# MCU152A_ADC.net
KiCad netlist of a schematic drawn in Altium Designer
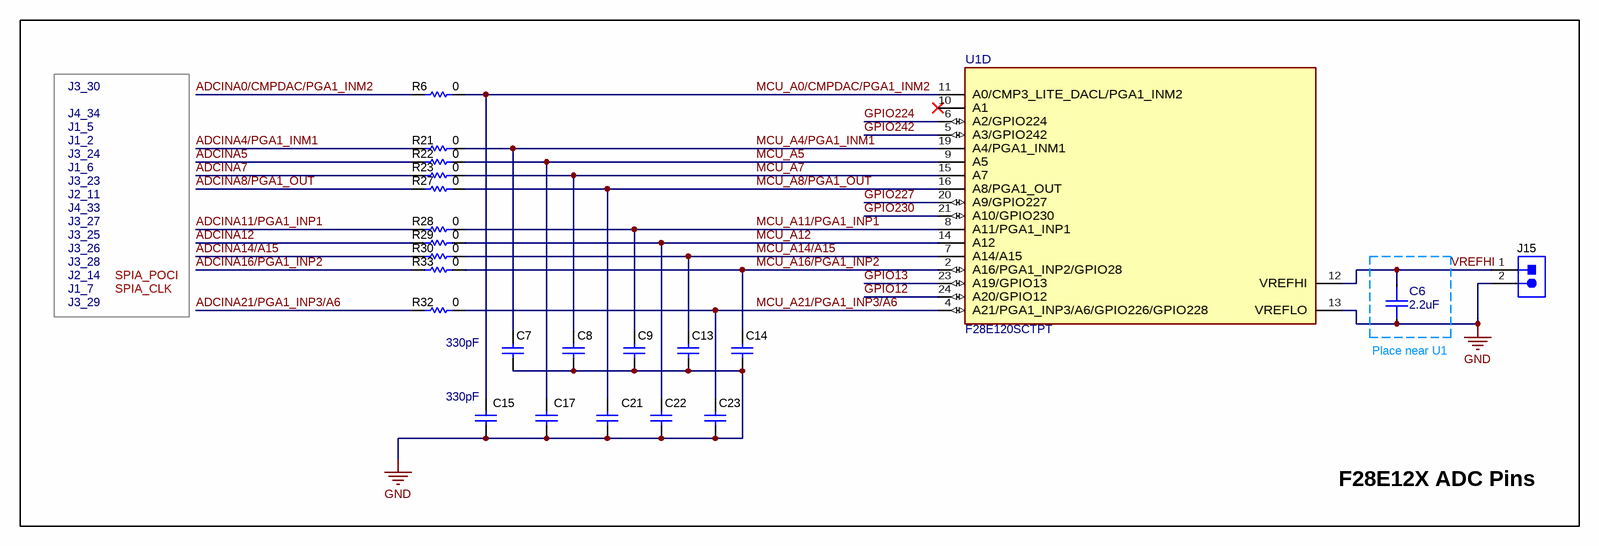
[diagram p0: MCU152A_ADC.SchDoc]

(export (version "E")
  (design (tool "Eeschema 10.0.6"))
  (components
    (comp (ref "C6")
      (value "885012106011")
      (footprint "FP-885012106011_0603-MFG")
      (description "2.2 µF ±20% 10V Ceramic Capacitor X5R 0603 (1608 Metric)")
      (fields
        (field (name "MANUFACTURER") "Wurth Electronics")
        (field (name "VALUEDISPLAYED") "2.2uF")
        (field (name "DIGIKEY PART NUMBER") "732-7908-1-ND")
      )
      (libsource (lib "Altium Vault - TI") (part "SYM-885012106011"))
    )
    (comp (ref "C7")
      (value "330pF")
      (footprint "0402")
      (description "CAP, CERM, 330 pF, 50 V, +/- 5%, C0G/NP0, 0402")
      (fields
        (field (name "MANUFACTURER") "MuRata")
        (field (name "PARTNUMBER") "GRM1555C1H331JA01D")
        (field (name "PUBLISHER") "Texas Instruments")
      )
      (libsource (lib "Altium Vault - TI") (part "Capacitor"))
    )
    (comp (ref "C8")
      (value "GRM1555C1H331JA01D")
      (footprint "0402")
      (description "CAP, CERM, 330 pF, 50 V, +/- 5%, C0G/NP0, 0402")
      (fields (field (name "MANUFACTURER") "MuRata") (field (name "PUBLISHER") "Texas Instruments"))
      (libsource (lib "Altium Vault - TI") (part "Capacitor"))
    )
    (comp (ref "C9")
      (value "GRM1555C1H331JA01D")
      (footprint "0402")
      (description "CAP, CERM, 330 pF, 50 V, +/- 5%, C0G/NP0, 0402")
      (fields (field (name "MANUFACTURER") "MuRata") (field (name "PUBLISHER") "Texas Instruments"))
      (libsource (lib "Altium Vault - TI") (part "Capacitor"))
    )
    (comp (ref "C13")
      (value "GRM1555C1H331JA01D")
      (footprint "0402")
      (description "CAP, CERM, 330 pF, 50 V, +/- 5%, C0G/NP0, 0402")
      (fields (field (name "MANUFACTURER") "MuRata") (field (name "PUBLISHER") "Texas Instruments"))
      (libsource (lib "Altium Vault - TI") (part "Capacitor"))
    )
    (comp (ref "C14")
      (value "GRM1555C1H331JA01D")
      (footprint "0402")
      (description "CAP, CERM, 330 pF, 50 V, +/- 5%, C0G/NP0, 0402")
      (fields (field (name "MANUFACTURER") "MuRata") (field (name "PUBLISHER") "Texas Instruments"))
      (libsource (lib "Altium Vault - TI") (part "Capacitor"))
    )
    (comp (ref "C15")
      (value "330pF")
      (footprint "0402")
      (description "CAP, CERM, 330 pF, 50 V, +/- 5%, C0G/NP0, 0402")
      (fields
        (field (name "MANUFACTURER") "MuRata")
        (field (name "PARTNUMBER") "GRM1555C1H331JA01D")
        (field (name "PUBLISHER") "Texas Instruments")
      )
      (libsource (lib "Altium Vault - TI") (part "Capacitor"))
    )
    (comp (ref "C17")
      (value "GRM1555C1H331JA01D")
      (footprint "0402")
      (description "CAP, CERM, 330 pF, 50 V, +/- 5%, C0G/NP0, 0402")
      (fields (field (name "MANUFACTURER") "MuRata") (field (name "PUBLISHER") "Texas Instruments"))
      (libsource (lib "Altium Vault - TI") (part "Capacitor"))
    )
    (comp (ref "C21")
      (value "GRM1555C1H331JA01D")
      (footprint "0402")
      (description "CAP, CERM, 330 pF, 50 V, +/- 5%, C0G/NP0, 0402")
      (fields (field (name "MANUFACTURER") "MuRata") (field (name "PUBLISHER") "Texas Instruments"))
      (libsource (lib "Altium Vault - TI") (part "Capacitor"))
    )
    (comp (ref "C22")
      (value "GRM1555C1H331JA01D")
      (footprint "0402")
      (description "CAP, CERM, 330 pF, 50 V, +/- 5%, C0G/NP0, 0402")
      (fields (field (name "MANUFACTURER") "MuRata") (field (name "PUBLISHER") "Texas Instruments"))
      (libsource (lib "Altium Vault - TI") (part "Capacitor"))
    )
    (comp (ref "C23")
      (value "GRM1555C1H331JA01D")
      (footprint "0402")
      (description "CAP, CERM, 330 pF, 50 V, +/- 5%, C0G/NP0, 0402")
      (fields (field (name "MANUFACTURER") "MuRata") (field (name "PUBLISHER") "Texas Instruments"))
      (libsource (lib "Altium Vault - TI") (part "Capacitor"))
    )
    (comp (ref "J15")
      (value "61300211121")
      (footprint "WURTH_61300211121")
      (description "Header, 2.54 mm, 2x1, Gold, TH")
      (fields (field (name "MANUFACTURER") "Wurth Elektronik") (field (name "PUBLISHER") "Texas Instruments"))
      (libsource (lib "Altium Vault - TI") (part "Header_2x1"))
    )
    (comp (ref "R6")
      (value "RC0402JR-070RL")
      (footprint "0402")
      (description "RES, 0, 5%, 0.063 W, 0402")
      (fields
        (field (name "MANUFACTURER") "Yageo America")
        (field (name "VALUEDISPLAYED") "0")
        (field (name "PUBLISHER") "Texas Instruments")
      )
      (libsource (lib "Altium Vault - TI") (part "Resistor"))
    )
    (comp (ref "R21")
      (value "RC0402JR-070RL")
      (footprint "0402")
      (description "RES, 0, 5%, 0.063 W, 0402")
      (fields
        (field (name "MANUFACTURER") "Yageo America")
        (field (name "VALUEDISPLAYED") "0")
        (field (name "PUBLISHER") "Texas Instruments")
      )
      (libsource (lib "Altium Vault - TI") (part "Resistor"))
    )
    (comp (ref "R22")
      (value "RC0402JR-070RL")
      (footprint "0402")
      (description "RES, 0, 5%, 0.063 W, 0402")
      (fields
        (field (name "MANUFACTURER") "Yageo America")
        (field (name "VALUEDISPLAYED") "0")
        (field (name "PUBLISHER") "Texas Instruments")
      )
      (libsource (lib "Altium Vault - TI") (part "Resistor"))
    )
    (comp (ref "R23")
      (value "RC0402JR-070RL")
      (footprint "0402")
      (description "RES, 0, 5%, 0.063 W, 0402")
      (fields
        (field (name "MANUFACTURER") "Yageo America")
        (field (name "VALUEDISPLAYED") "0")
        (field (name "PUBLISHER") "Texas Instruments")
      )
      (libsource (lib "Altium Vault - TI") (part "Resistor"))
    )
    (comp (ref "R27")
      (value "RC0402JR-070RL")
      (footprint "0402")
      (description "RES, 0, 5%, 0.063 W, 0402")
      (fields
        (field (name "MANUFACTURER") "Yageo America")
        (field (name "VALUEDISPLAYED") "0")
        (field (name "PUBLISHER") "Texas Instruments")
      )
      (libsource (lib "Altium Vault - TI") (part "Resistor"))
    )
    (comp (ref "R28")
      (value "RC0402JR-070RL")
      (footprint "0402")
      (description "RES, 0, 5%, 0.063 W, 0402")
      (fields
        (field (name "MANUFACTURER") "Yageo America")
        (field (name "VALUEDISPLAYED") "0")
        (field (name "PUBLISHER") "Texas Instruments")
      )
      (libsource (lib "Altium Vault - TI") (part "Resistor"))
    )
    (comp (ref "R29")
      (value "RC0402JR-070RL")
      (footprint "0402")
      (description "RES, 0, 5%, 0.063 W, 0402")
      (fields
        (field (name "MANUFACTURER") "Yageo America")
        (field (name "VALUEDISPLAYED") "0")
        (field (name "PUBLISHER") "Texas Instruments")
      )
      (libsource (lib "Altium Vault - TI") (part "Resistor"))
    )
    (comp (ref "R30")
      (value "RC0402JR-070RL")
      (footprint "0402")
      (description "RES, 0, 5%, 0.063 W, 0402")
      (fields
        (field (name "MANUFACTURER") "Yageo America")
        (field (name "VALUEDISPLAYED") "0")
        (field (name "PUBLISHER") "Texas Instruments")
      )
      (libsource (lib "Altium Vault - TI") (part "Resistor"))
    )
    (comp (ref "R32")
      (value "RC0402JR-070RL")
      (footprint "0402")
      (description "RES, 0, 5%, 0.063 W, 0402")
      (fields
        (field (name "MANUFACTURER") "Yageo America")
        (field (name "VALUEDISPLAYED") "0")
        (field (name "PUBLISHER") "Texas Instruments")
      )
      (libsource (lib "Altium Vault - TI") (part "Resistor"))
    )
    (comp (ref "R33")
      (value "RC0402JR-070RL")
      (footprint "0402")
      (description "RES, 0, 5%, 0.063 W, 0402")
      (fields
        (field (name "MANUFACTURER") "Yageo America")
        (field (name "VALUEDISPLAYED") "0")
        (field (name "PUBLISHER") "Texas Instruments")
      )
      (libsource (lib "Altium Vault - TI") (part "Resistor"))
    )
    (comp (ref "U1")
      (value "F28E120SCTPT")
      (footprint "PT0048A-MFG")
      (description "F28E12x Real-Time Microcontrollers")
      (fields (field (name "MANUFACTURER") "Texas Instruments") (field (name "PARTNUMBER") "F28E120SCTPT"))
      (libsource (lib "Altium Vault - TI") (part "SYM-F28E120SCTPT"))
    )
  )
  (nets
    (net (code "1") (name "/ADCINA0{slash}CMPDAC{slash}PGA1_INM2") (class "Default")
      (node (ref "R6") (pin "1") (pinfunction "1_1") (pintype "passive"))
    )
    (net (code "2") (name "/ADCINA4{slash}PGA1_INM1") (class "Default")
      (node (ref "R21") (pin "1") (pinfunction "1_1") (pintype "passive"))
    )
    (net (code "3") (name "/ADCINA5") (class "Default")
      (node (ref "R22") (pin "1") (pinfunction "1_1") (pintype "passive"))
    )
    (net (code "4") (name "/ADCINA7") (class "Default")
      (node (ref "R23") (pin "1") (pinfunction "1_1") (pintype "passive"))
    )
    (net (code "5") (name "/ADCINA8{slash}PGA1_OUT") (class "Default")
      (node (ref "R27") (pin "1") (pinfunction "1_1") (pintype "passive"))
    )
    (net (code "6") (name "/ADCINA11{slash}PGA1_INP1") (class "Default")
      (node (ref "R28") (pin "1") (pinfunction "1_1") (pintype "passive"))
    )
    (net (code "7") (name "/ADCINA12") (class "Default")
      (node (ref "R29") (pin "1") (pinfunction "1_1") (pintype "passive"))
    )
    (net (code "8") (name "/ADCINA14{slash}A15") (class "Default")
      (node (ref "R30") (pin "1") (pinfunction "1_1") (pintype "passive"))
    )
    (net (code "9") (name "/ADCINA16{slash}PGA1_INP2") (class "Default")
      (node (ref "R33") (pin "1") (pinfunction "1_1") (pintype "passive"))
    )
    (net (code "10") (name "/ADCINA21{slash}PGA1_INP3{slash}A6") (class "Default")
      (node (ref "R32") (pin "1") (pinfunction "1_1") (pintype "passive"))
    )
    (net (code "11") (name "/GPIO12") (class "Default")
      (node (ref "U1") (pin "24") (pinfunction "A20/GPIO12_24") (pintype "bidirectional"))
    )
    (net (code "12") (name "/GPIO13") (class "Default")
      (node (ref "U1") (pin "23") (pinfunction "A19/GPIO13_23") (pintype "bidirectional"))
    )
    (net (code "13") (name "/GPIO224") (class "Default")
      (node (ref "U1") (pin "6") (pinfunction "A2/GPIO224_6") (pintype "bidirectional"))
    )
    (net (code "14") (name "/GPIO227") (class "Default")
      (node (ref "U1") (pin "20") (pinfunction "A9/GPIO227_20") (pintype "bidirectional"))
    )
    (net (code "15") (name "/GPIO230") (class "Default")
      (node (ref "U1") (pin "21") (pinfunction "A10/GPIO230_21") (pintype "bidirectional"))
    )
    (net (code "16") (name "/GPIO242") (class "Default")
      (node (ref "U1") (pin "5") (pinfunction "A3/GPIO242_5") (pintype "bidirectional"))
    )
    (net (code "17") (name "/MCU_A0{slash}CMPDAC{slash}PGA1_INM2") (class "Default")
      (node (ref "C15") (pin "1") (pinfunction "1_1") (pintype "passive"))
      (node (ref "R6") (pin "2") (pinfunction "2_2") (pintype "passive"))
      (node (ref "U1") (pin "11") (pinfunction "A0/CMP3_LITE_DACL/PGA1_INM2_11") (pintype "passive"))
    )
    (net (code "18") (name "/MCU_A4{slash}PGA1_INM1") (class "Default")
      (node (ref "C7") (pin "1") (pinfunction "1_1") (pintype "passive"))
      (node (ref "R21") (pin "2") (pinfunction "2_2") (pintype "passive"))
      (node (ref "U1") (pin "19") (pinfunction "A4/PGA1_INM1_19") (pintype "passive"))
    )
    (net (code "19") (name "/MCU_A5") (class "Default")
      (node (ref "C17") (pin "1") (pinfunction "1_1") (pintype "passive"))
      (node (ref "R22") (pin "2") (pinfunction "2_2") (pintype "passive"))
      (node (ref "U1") (pin "9") (pinfunction "A5_9") (pintype "passive"))
    )
    (net (code "20") (name "/MCU_A7") (class "Default")
      (node (ref "C8") (pin "1") (pinfunction "1_1") (pintype "passive"))
      (node (ref "R23") (pin "2") (pinfunction "2_2") (pintype "passive"))
      (node (ref "U1") (pin "15") (pinfunction "A7_15") (pintype "passive"))
    )
    (net (code "21") (name "/MCU_A8{slash}PGA1_OUT") (class "Default")
      (node (ref "C21") (pin "1") (pinfunction "1_1") (pintype "passive"))
      (node (ref "R27") (pin "2") (pinfunction "2_2") (pintype "passive"))
      (node (ref "U1") (pin "16") (pinfunction "A8/PGA1_OUT_16") (pintype "passive"))
    )
    (net (code "22") (name "/MCU_A11{slash}PGA1_INP1") (class "Default")
      (node (ref "C9") (pin "1") (pinfunction "1_1") (pintype "passive"))
      (node (ref "R28") (pin "2") (pinfunction "2_2") (pintype "passive"))
      (node (ref "U1") (pin "8") (pinfunction "A11/PGA1_INP1_8") (pintype "passive"))
    )
    (net (code "23") (name "/MCU_A12") (class "Default")
      (node (ref "C22") (pin "1") (pinfunction "1_1") (pintype "passive"))
      (node (ref "R29") (pin "2") (pinfunction "2_2") (pintype "passive"))
      (node (ref "U1") (pin "14") (pinfunction "A12_14") (pintype "passive"))
    )
    (net (code "24") (name "/MCU_A14{slash}A15") (class "Default")
      (node (ref "C13") (pin "1") (pinfunction "1_1") (pintype "passive"))
      (node (ref "R30") (pin "2") (pinfunction "2_2") (pintype "passive"))
      (node (ref "U1") (pin "7") (pinfunction "A14/A15_7") (pintype "passive"))
    )
    (net (code "25") (name "/MCU_A16{slash}PGA1_INP2") (class "Default")
      (node (ref "C14") (pin "1") (pinfunction "1_1") (pintype "passive"))
      (node (ref "R33") (pin "2") (pinfunction "2_2") (pintype "passive"))
      (node (ref "U1") (pin "2") (pinfunction "A16/PGA1_INP2/GPIO28_2") (pintype "bidirectional"))
    )
    (net (code "26") (name "/MCU_A21{slash}PGA1_INP3{slash}A6") (class "Default")
      (node (ref "C23") (pin "1") (pinfunction "1_1") (pintype "passive"))
      (node (ref "R32") (pin "2") (pinfunction "2_2") (pintype "passive"))
      (node (ref "U1") (pin "4") (pinfunction "A21/PGA1_INP3/A6/GPIO226/GPIO228_4") (pintype "bidirectional"))
    )
    (net (code "27") (name "/VREFHI") (class "Default")
      (node (ref "C6") (pin "1") (pinfunction "1_1") (pintype "passive"))
      (node (ref "J15") (pin "1") (pinfunction "1_1") (pintype "passive"))
      (node (ref "U1") (pin "12") (pinfunction "VREFHI_12") (pintype "power_in"))
    )
    (net (code "28") (name "GND") (class "Default")
      (node (ref "C13") (pin "2") (pinfunction "2_2") (pintype "passive"))
      (node (ref "C14") (pin "2") (pinfunction "2_2") (pintype "passive"))
      (node (ref "C15") (pin "2") (pinfunction "2_2") (pintype "passive"))
      (node (ref "C17") (pin "2") (pinfunction "2_2") (pintype "passive"))
      (node (ref "C21") (pin "2") (pinfunction "2_2") (pintype "passive"))
      (node (ref "C22") (pin "2") (pinfunction "2_2") (pintype "passive"))
      (node (ref "C23") (pin "2") (pinfunction "2_2") (pintype "passive"))
      (node (ref "C6") (pin "2") (pinfunction "2_2") (pintype "passive"))
      (node (ref "C7") (pin "2") (pinfunction "2_2") (pintype "passive"))
      (node (ref "C8") (pin "2") (pinfunction "2_2") (pintype "passive"))
      (node (ref "C9") (pin "2") (pinfunction "2_2") (pintype "passive"))
      (node (ref "J15") (pin "2") (pinfunction "2_2") (pintype "passive"))
      (node (ref "U1") (pin "13") (pinfunction "VREFLO_13") (pintype "power_in"))
    )
    (net (code "29") (name "unconnected-(U1D-A1-Pad10)") (class "Default")
      (node (ref "U1") (pin "10") (pinfunction "A1_10") (pintype "passive+no_connect"))
    )
  )
)
